# Power_test.net
KiCad netlist of a schematic drawn in Altium Designer
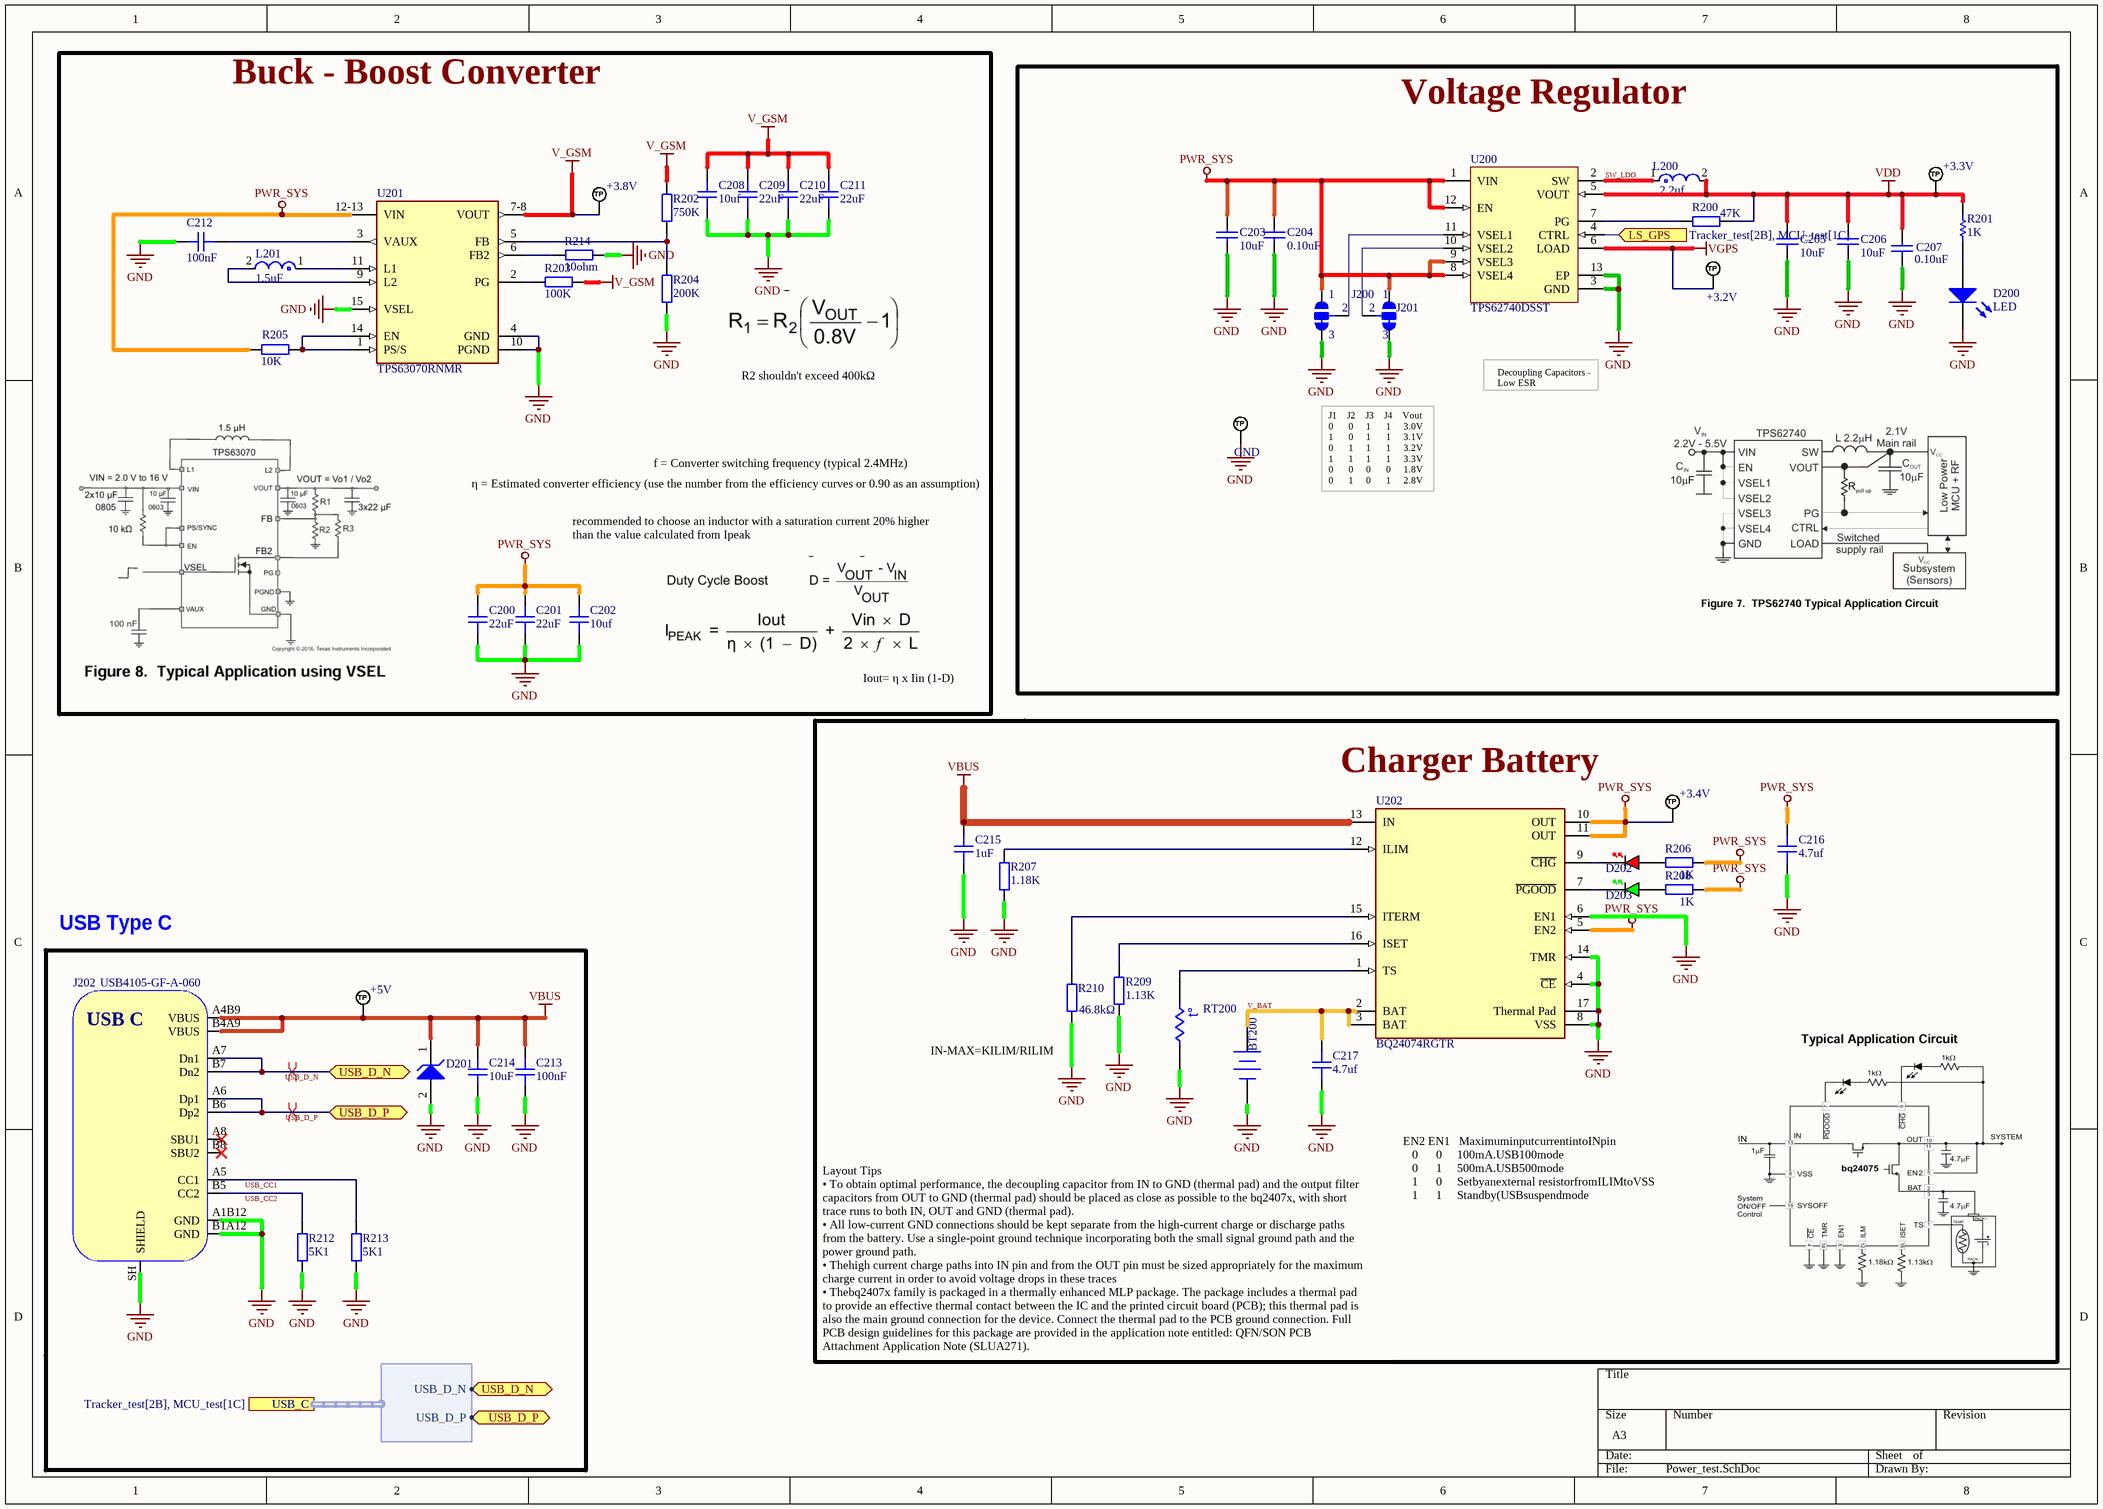
[diagram p0: Power_test.SchDoc]

(export (version "E")
  (design (tool "Eeschema 10.0.6"))
  (components
    (comp (ref "+3.2V")
      (value "TP_NOBOM")
      (footprint "PAD_RND_1MM")
      (description "Test Point Round 1mm (NO BOM)")
      (libsource (lib "PhilsLab_Library") (part "TEST_POINT_RND_1MM"))
    )
    (comp (ref "+3.3V")
      (value "TP_NOBOM")
      (footprint "PAD_RND_1MM")
      (description "Test Point Round 1mm (NO BOM)")
      (libsource (lib "PhilsLab_Library") (part "TEST_POINT_RND_1MM"))
    )
    (comp (ref "+3.4V")
      (value "TP_NOBOM")
      (footprint "PAD_RND_1MM")
      (description "Test Point Round 1mm (NO BOM)")
      (libsource (lib "PhilsLab_Library") (part "TEST_POINT_RND_1MM"))
    )
    (comp (ref "+3.8V")
      (value "TP_NOBOM")
      (footprint "PAD_RND_1MM")
      (description "Test Point Round 1mm (NO BOM)")
      (libsource (lib "PhilsLab_Library") (part "TEST_POINT_RND_1MM"))
    )
    (comp (ref "+5V")
      (value "TP_NOBOM")
      (footprint "PAD_RND_1MM")
      (description "Test Point Round 1mm (NO BOM)")
      (libsource (lib "PhilsLab_Library") (part "TEST_POINT_RND_1MM"))
    )
    (comp (ref "BT200")
      (value "Battery")
      (footprint "BAT-2")
      (description "Multicell Battery")
      (fields (field (name "PUBLISHER") "Altium Limited"))
      (libsource (lib "Miscellaneous+Devices") (part "Battery"))
    )
    (comp (ref "C200")
      (value "22uF")
      (footprint "CAP_0805")
      (description "Capacitor SMD 0805")
      (libsource (lib "PhilsLab_Library") (part "CAP_0805"))
    )
    (comp (ref "C201")
      (value "22uF")
      (footprint "CAP_0805")
      (description "Capacitor SMD 0805")
      (libsource (lib "PhilsLab_Library") (part "CAP_0805"))
    )
    (comp (ref "C202")
      (value "10uf")
      (footprint "CAP_0603")
      (description "Capacitor SMD 0603")
      (libsource (lib "PhilsLab_Library") (part "CAP_0603"))
    )
    (comp (ref "C203")
      (value "10uF")
      (footprint "C0402 - duplicate")
      (description "CAP CER 10UF 10V X5R 0402")
      (fields
        (field (name "PART NUMBER") "C00062")
        (field (name "MANUFACTURER") "KEMET - Electronic Component")
      )
      (libsource (lib "intrgrat_lib") (part "CAP"))
    )
    (comp (ref "C204")
      (value "0.10uF")
      (footprint "C0402")
      (description "CAP CER 0.1UF 10V X5R 0402")
      (fields
        (field (name "PART NUMBER") "C00062")
        (field (name "MANUFACTURER") "KEMET - Electronic Component")
      )
      (libsource (lib "intrgrat_lib") (part "CAP_2"))
    )
    (comp (ref "C205")
      (value "10uF")
      (footprint "C0402 - duplicate")
      (description "CAP CER 10UF 10V X5R 0402")
      (fields
        (field (name "PART NUMBER") "C00062")
        (field (name "MANUFACTURER") "KEMET - Electronic Component")
      )
      (libsource (lib "intrgrat_lib") (part "CAP"))
    )
    (comp (ref "C206")
      (value "10uF")
      (footprint "C0402 - duplicate")
      (description "CAP CER 10UF 10V X5R 0402")
      (fields
        (field (name "PART NUMBER") "C00062")
        (field (name "MANUFACTURER") "KEMET - Electronic Component")
      )
      (libsource (lib "intrgrat_lib") (part "CAP"))
    )
    (comp (ref "C207")
      (value "0.10uF")
      (footprint "C0402")
      (description "CAP CER 0.1UF 10V X5R 0402")
      (fields
        (field (name "PART NUMBER") "C00062")
        (field (name "MANUFACTURER") "KEMET - Electronic Component")
      )
      (libsource (lib "intrgrat_lib") (part "CAP_2"))
    )
    (comp (ref "C208")
      (value "10uf")
      (footprint "CAP_0603")
      (description "Capacitor SMD 0603")
      (libsource (lib "PhilsLab_Library") (part "CAP_0603"))
    )
    (comp (ref "C209")
      (value "22uF")
      (footprint "CAP_0805")
      (description "Capacitor SMD 0805")
      (libsource (lib "PhilsLab_Library") (part "CAP_0805"))
    )
    (comp (ref "C210")
      (value "22uF")
      (footprint "CAP_0805")
      (description "Capacitor SMD 0805")
      (libsource (lib "PhilsLab_Library") (part "CAP_0805"))
    )
    (comp (ref "C211")
      (value "22uF")
      (footprint "CAP_0805")
      (description "Capacitor SMD 0805")
      (libsource (lib "PhilsLab_Library") (part "CAP_0805"))
    )
    (comp (ref "C212")
      (value "100nF")
      (footprint "CAP_0603")
      (description "Capacitor SMD 0603")
      (libsource (lib "PhilsLab_Library") (part "CAP_0603"))
    )
    (comp (ref "C213")
      (value "100nF")
      (footprint "CAP_0402")
      (description "Capacitor SMD 0402")
      (libsource (lib "PhilsLab_Library") (part "CAP_0402"))
    )
    (comp (ref "C214")
      (value "10uF")
      (footprint "CAP_0402")
      (description "Capacitor SMD 0402")
      (libsource (lib "PhilsLab_Library") (part "CAP_0402"))
    )
    (comp (ref "C215")
      (value "1uF")
      (footprint "CAP_0402")
      (description "Capacitor SMD 0402")
      (libsource (lib "PhilsLab_Library") (part "CAP_0402"))
    )
    (comp (ref "C216")
      (value "4.7uf")
      (footprint "CAP_0402")
      (description "Capacitor SMD 0402")
      (libsource (lib "PhilsLab_Library") (part "CAP_0402"))
    )
    (comp (ref "C217")
      (value "4.7uf")
      (footprint "CAP_0402")
      (description "Capacitor SMD 0402")
      (libsource (lib "PhilsLab_Library") (part "CAP_0402"))
    )
    (comp (ref "D200")
      (value "LED")
      (footprint "LED-0603-R")
      (description "Typical RED GaAs LED")
      (fields
        (field (name "MANUFACTURER") "Lite-On Inc.")
        (field (name "PARTNUMBER") "LTST-C190GKT")
        (field (name "PUBLISHER") "Walid Balid")
      )
      (libsource (lib "intrgrat_lib") (part "LED"))
    )
    (comp (ref "D201")
      (value "SZSMF6.0AT1G")
      (footprint "ONSC-SOD-123FL-2-498_V")
      (description "200 W Transient Voltage Suppressor, 2-Pin SOD-123FL, Pb-Free, Tape and Reel")
      (fields (field (name "MANUFACTURER") "On Semiconductor"))
      (libsource (lib "Altium Content Vault") (part "ONSC-K1A2-2"))
    )
    (comp (ref "D202")
      (value "RED")
      (footprint "LED_0402_RED")
      (description "LED 0402 RED SMD")
      (libsource (lib "PhilsLab_Library") (part "LED_0402_RED"))
    )
    (comp (ref "D203")
      (value "GREEN")
      (footprint "LED_0402_GREEN")
      (description "LED 0402 GREEN SMD")
      (libsource (lib "PhilsLab_Library") (part "LED_0402_GREEN"))
    )
    (comp (ref "GND")
      (value "TP_NOBOM")
      (footprint "PAD_RND_1MM")
      (description "Test Point Round 1mm (NO BOM)")
      (libsource (lib "PhilsLab_Library") (part "TEST_POINT_RND_1MM"))
    )
    (comp (ref "J200")
      (value "JUMPER-3-PAD")
      (footprint "JUMPER-3-NC")
      (libsource (lib "intrgrat_lib") (part "JUMPER-3-PAD"))
    )
    (comp (ref "J201")
      (value "JUMPER-3-PAD")
      (footprint "JUMPER-3-NC")
      (libsource (lib "") (part "JUMPER-3-PAD_1"))
    )
    (comp (ref "J202")
      (value "USB4105-GF-A-060")
      (footprint "USB4105-GF-A-060")
      (description "USB Connector Type C SMT 12 Pin")
      (fields (field (name "MANUFACTURER") "GCT"))
      (libsource (lib "Schematic-Lib-PhilsLab") (part "USB4105-GF-A-060"))
    )
    (comp (ref "L200")
      (value "2.2uf")
      (footprint "FP-LPS3314-MFG")
      (libsource (lib "Altium Content Vault") (part "4cc4b267dca4c8e51f7102f422741d8"))
    )
    (comp (ref "L201")
      (value "1.5uF")
      (footprint "FP-XFL4020-MFG")
      (fields (field (name "TOLERANCE") "20%"))
      (libsource (lib "") (part "4cc4b267dca4c8e51f7102f422741d8_1"))
    )
    (comp (ref "R200")
      (value "47K")
      (footprint "RES_0402")
      (description "Resistor SMD 0402")
      (libsource (lib "PhilsLab_Library") (part "RES_0402"))
    )
    (comp (ref "R201")
      (value "1K")
      (footprint "R0402")
      (description "RES SMD 1K OHM 5% 1/16W 0402")
      (fields (field (name "PART NUMBER") "R00007") (field (name "MANUFACTURER") "Yageo"))
      (libsource (lib "intrgrat_lib") (part "RES"))
    )
    (comp (ref "R202")
      (value "750K")
      (footprint "RES_0402")
      (description "Resistor SMD 0402")
      (libsource (lib "PhilsLab_Library") (part "RES_0402"))
    )
    (comp (ref "R203")
      (value "100K")
      (footprint "RES_0402")
      (description "Resistor SMD 0402")
      (libsource (lib "PhilsLab_Library") (part "RES_0402"))
    )
    (comp (ref "R204")
      (value "200K")
      (footprint "RES_0402")
      (description "Resistor SMD 0402")
      (libsource (lib "PhilsLab_Library") (part "RES_0402"))
    )
    (comp (ref "R205")
      (value "10K")
      (footprint "RES_0402")
      (description "Resistor SMD 0402")
      (libsource (lib "PhilsLab_Library") (part "RES_0402"))
    )
    (comp (ref "R206")
      (value "1K")
      (footprint "RES_0402")
      (description "Resistor SMD 0402")
      (libsource (lib "PhilsLab_Library") (part "RES_0402"))
    )
    (comp (ref "R207")
      (value "1.18K")
      (footprint "RES_0402")
      (description "Resistor SMD 0402")
      (libsource (lib "PhilsLab_Library") (part "RES_0402"))
    )
    (comp (ref "R208")
      (value "1K")
      (footprint "RES_0402")
      (description "Resistor SMD 0402")
      (libsource (lib "PhilsLab_Library") (part "RES_0402"))
    )
    (comp (ref "R209")
      (value "1.13K")
      (footprint "RES_0402")
      (description "Resistor SMD 0402")
      (libsource (lib "PhilsLab_Library") (part "RES_0402"))
    )
    (comp (ref "R210")
      (value "46.8kΩ")
      (footprint "RES_0402")
      (description "Resistor SMD 0402")
      (libsource (lib "PhilsLab_Library") (part "RES_0402"))
    )
    (comp (ref "R212")
      (value "5K1")
      (footprint "RES_0603")
      (description "Resistor SMD 0603")
      (libsource (lib "Schematic-Lib-PhilsLab") (part "RES_0603"))
    )
    (comp (ref "R213")
      (value "5K1")
      (footprint "RES_0603")
      (description "Resistor SMD 0603")
      (libsource (lib "Schematic-Lib-PhilsLab") (part "RES_0603"))
    )
    (comp (ref "R214")
      (value "10ohm")
      (footprint "RES_0402")
      (description "Resistor SMD 0402")
      (libsource (lib "PhilsLab_Library") (part "RES_0402"))
    )
    (comp (ref "RT200")
      (value "Res Thermal")
      (footprint "6-0805_N")
      (description "Thermistor")
      (fields (field (name "PUBLISHER") "Altium Limited"))
      (libsource (lib "intrgrat_lib") (part "Res Thermal"))
    )
    (comp (ref "U200")
      (value "TPS62740DSST")
      (footprint "DSS0012A_V")
      (fields (field (name "PARTNUMBER") "TPS62740"))
      (libsource (lib "intrgrat_lib") (part "CMP-0323-00573-2"))
    )
    (comp (ref "U201")
      (value "TPS63070RNMR")
      (footprint "FP-RNM0015A-MFG")
      (description "IC REG BCK BST ADJ 3.6A 15VQFN")
      (libsource (lib "intrgrat_lib") (part "CMP-04918-000409-1"))
    )
    (comp (ref "U202")
      (value "BQ24074RGTR")
      (footprint "FP-RGT0016C-MFG")
      (description "IC LI-ION CHARGE MGMT 16-QFN")
      (libsource (lib "intrgrat_lib") (part "CMP-0321-00220-3"))
    )
  )
  (nets
    (net (code "2") (name "/LS_GPS") (class "Default")
      (node (ref "U200") (pin "4") (pinfunction "CTRL_4") (pintype "input"))
    )
    (net (code "3") (name "/SW_LDO") (class "Default")
      (node (ref "L200") (pin "1") (pinfunction "1_1") (pintype "passive"))
      (node (ref "U200") (pin "2") (pinfunction "SW_2") (pintype "power_in"))
    )
    (net (code "4") (name "/USB_CC1") (class "Default")
      (node (ref "J202") (pin "A5") (pinfunction "CC1_A5") (pintype "passive"))
      (node (ref "R213") (pin "2") (pinfunction "2_2") (pintype "passive"))
    )
    (net (code "5") (name "/USB_CC2") (class "Default")
      (node (ref "J202") (pin "B5") (pinfunction "CC2_B5") (pintype "passive"))
      (node (ref "R212") (pin "2") (pinfunction "2_2") (pintype "passive"))
    )
    (net (code "6") (name "/USB_D_N") (class "Default")
      (node (ref "J202") (pin "A7") (pinfunction "Dn1_A7") (pintype "passive"))
      (node (ref "J202") (pin "B7") (pinfunction "Dn2_B7") (pintype "passive"))
    )
    (net (code "7") (name "/USB_D_P") (class "Default")
      (node (ref "J202") (pin "A6") (pinfunction "Dp1_A6") (pintype "passive"))
      (node (ref "J202") (pin "B6") (pinfunction "Dp2_B6") (pintype "passive"))
    )
    (net (code "8") (name "/V_BAT") (class "Default")
      (node (ref "BT200") (pin "1") (pinfunction "+_1") (pintype "passive"))
      (node (ref "C217") (pin "1") (pinfunction "1_1") (pintype "passive"))
      (node (ref "U202") (pin "2") (pinfunction "BAT_2") (pintype "power_in"))
      (node (ref "U202") (pin "3") (pinfunction "BAT_3") (pintype "power_in"))
    )
    (net (code "10") (name "GND") (class "Default")
      (node (ref "BT200") (pin "2") (pinfunction "-_2") (pintype "passive"))
      (node (ref "C200") (pin "1") (pinfunction "1_1") (pintype "passive"))
      (node (ref "C201") (pin "1") (pinfunction "1_1") (pintype "passive"))
      (node (ref "C202") (pin "1") (pinfunction "1_1") (pintype "passive"))
      (node (ref "C203") (pin "2") (pinfunction "2_2") (pintype "passive"))
      (node (ref "C204") (pin "2") (pinfunction "2_2") (pintype "passive"))
      (node (ref "C205") (pin "2") (pinfunction "2_2") (pintype "passive"))
      (node (ref "C206") (pin "2") (pinfunction "2_2") (pintype "passive"))
      (node (ref "C207") (pin "2") (pinfunction "2_2") (pintype "passive"))
      (node (ref "C208") (pin "1") (pinfunction "1_1") (pintype "passive"))
      (node (ref "C209") (pin "1") (pinfunction "1_1") (pintype "passive"))
      (node (ref "C210") (pin "1") (pinfunction "1_1") (pintype "passive"))
      (node (ref "C211") (pin "1") (pinfunction "1_1") (pintype "passive"))
      (node (ref "C212") (pin "1") (pinfunction "1_1") (pintype "passive"))
      (node (ref "C213") (pin "1") (pinfunction "1_1") (pintype "passive"))
      (node (ref "C214") (pin "1") (pinfunction "1_1") (pintype "passive"))
      (node (ref "C215") (pin "1") (pinfunction "1_1") (pintype "passive"))
      (node (ref "C216") (pin "2") (pinfunction "2_2") (pintype "passive"))
      (node (ref "C217") (pin "2") (pinfunction "2_2") (pintype "passive"))
      (node (ref "D200") (pin "2") (pinfunction "K_2") (pintype "passive"))
      (node (ref "D201") (pin "2") (pinfunction "A_2") (pintype "passive"))
      (node (ref "GND") (pin "1") (pinfunction "TP_1") (pintype "passive"))
      (node (ref "J200") (pin "3") (pinfunction "3_3") (pintype "passive"))
      (node (ref "J201") (pin "3") (pinfunction "3_3") (pintype "passive"))
      (node (ref "J202") (pin "A1B12") (pinfunction "GND_A1B12") (pintype "passive"))
      (node (ref "J202") (pin "B1A12") (pinfunction "GND_B1A12") (pintype "passive"))
      (node (ref "J202") (pin "SH") (pinfunction "SHIELD_SH") (pintype "passive"))
      (node (ref "R204") (pin "1") (pinfunction "1_1") (pintype "passive"))
      (node (ref "R207") (pin "1") (pinfunction "1_1") (pintype "passive"))
      (node (ref "R209") (pin "1") (pinfunction "1_1") (pintype "passive"))
      (node (ref "R210") (pin "2") (pinfunction "2_2") (pintype "passive"))
      (node (ref "R212") (pin "1") (pinfunction "1_1") (pintype "passive"))
      (node (ref "R213") (pin "1") (pinfunction "1_1") (pintype "passive"))
      (node (ref "R214") (pin "1") (pinfunction "1_1") (pintype "passive"))
      (node (ref "RT200") (pin "2") (pinfunction "2_2") (pintype "passive"))
      (node (ref "U200") (pin "13") (pinfunction "EP_13") (pintype "power_in"))
      (node (ref "U200") (pin "3") (pinfunction "GND_3") (pintype "power_in"))
      (node (ref "U201") (pin "10") (pinfunction "PGND_10") (pintype "power_in"))
      (node (ref "U201") (pin "15") (pinfunction "VSEL_15") (pintype "input"))
      (node (ref "U201") (pin "4") (pinfunction "GND_4") (pintype "power_in"))
      (node (ref "U202") (pin "14") (pinfunction "TMR_14") (pintype "input"))
      (node (ref "U202") (pin "17") (pinfunction "Thermal_Pad_17") (pintype "power_in"))
      (node (ref "U202") (pin "4") (pinfunction "~{CE}_4") (pintype "input"))
      (node (ref "U202") (pin "6") (pinfunction "EN1_6") (pintype "input"))
      (node (ref "U202") (pin "8") (pinfunction "VSS_8") (pintype "power_in"))
    )
    (net (code "11") (name "Net-(D200-A)") (class "Default")
      (node (ref "D200") (pin "1") (pinfunction "A_1") (pintype "passive"))
      (node (ref "R201") (pin "2") (pinfunction "2_2") (pintype "passive"))
    )
    (net (code "12") (name "Net-(D202-PadA)") (class "Default")
      (node (ref "D202") (pin "A") (pinfunction "A_A") (pintype "passive"))
      (node (ref "R206") (pin "1") (pinfunction "1_1") (pintype "passive"))
    )
    (net (code "13") (name "Net-(D203-PadA)") (class "Default")
      (node (ref "D203") (pin "A") (pinfunction "A_A") (pintype "passive"))
      (node (ref "R208") (pin "1") (pinfunction "1_1") (pintype "passive"))
    )
    (net (code "14") (name "Net-(U200-PG)") (class "Default")
      (node (ref "R200") (pin "1") (pinfunction "1_1") (pintype "passive"))
      (node (ref "U200") (pin "7") (pinfunction "PG_7") (pintype "tri_state"))
    )
    (net (code "15") (name "Net-(U200-VSEL1)") (class "Default")
      (node (ref "J200") (pin "2") (pinfunction "2_2") (pintype "passive"))
      (node (ref "U200") (pin "11") (pinfunction "VSEL1_11") (pintype "input"))
    )
    (net (code "16") (name "Net-(U200-VSEL2)") (class "Default")
      (node (ref "J201") (pin "2") (pinfunction "2_2") (pintype "passive"))
      (node (ref "U200") (pin "10") (pinfunction "VSEL2_10") (pintype "input"))
    )
    (net (code "17") (name "Net-(U201-EN)") (class "Default")
      (node (ref "R205") (pin "2") (pinfunction "2_2") (pintype "passive"))
      (node (ref "U201") (pin "1") (pinfunction "PS/S_1") (pintype "input"))
      (node (ref "U201") (pin "14") (pinfunction "EN_14") (pintype "input"))
    )
    (net (code "18") (name "Net-(U201-FB)") (class "Default")
      (node (ref "R202") (pin "1") (pinfunction "1_1") (pintype "passive"))
      (node (ref "R204") (pin "2") (pinfunction "2_2") (pintype "passive"))
      (node (ref "U201") (pin "5") (pinfunction "FB_5") (pintype "output"))
    )
    (net (code "19") (name "Net-(U201-FB2)") (class "Default")
      (node (ref "R214") (pin "2") (pinfunction "2_2") (pintype "passive"))
      (node (ref "U201") (pin "6") (pinfunction "FB2_6") (pintype "output"))
    )
    (net (code "20") (name "Net-(U201-L1)") (class "Default")
      (node (ref "L201") (pin "1") (pinfunction "1_1") (pintype "passive"))
      (node (ref "U201") (pin "11") (pinfunction "L1_11") (pintype "input"))
    )
    (net (code "21") (name "Net-(U201-L2)") (class "Default")
      (node (ref "L201") (pin "2") (pinfunction "2_2") (pintype "passive"))
      (node (ref "U201") (pin "9") (pinfunction "L2_9") (pintype "input"))
    )
    (net (code "22") (name "Net-(U201-PG)") (class "Default")
      (node (ref "R203") (pin "2") (pinfunction "2_2") (pintype "passive"))
      (node (ref "U201") (pin "2") (pinfunction "PG_2") (pintype "open_collector"))
    )
    (net (code "23") (name "Net-(U201-VAUX)") (class "Default")
      (node (ref "C212") (pin "2") (pinfunction "2_2") (pintype "passive"))
      (node (ref "U201") (pin "3") (pinfunction "VAUX_3") (pintype "output"))
    )
    (net (code "24") (name "Net-(U202-ILIM)") (class "Default")
      (node (ref "R207") (pin "2") (pinfunction "2_2") (pintype "passive"))
      (node (ref "U202") (pin "12") (pinfunction "ILIM_12") (pintype "input"))
    )
    (net (code "25") (name "Net-(U202-ISET)") (class "Default")
      (node (ref "R209") (pin "2") (pinfunction "2_2") (pintype "passive"))
      (node (ref "U202") (pin "16") (pinfunction "ISET_16") (pintype "input"))
    )
    (net (code "26") (name "Net-(U202-ITERM)") (class "Default")
      (node (ref "R210") (pin "1") (pinfunction "1_1") (pintype "passive"))
      (node (ref "U202") (pin "15") (pinfunction "ITERM_15") (pintype "input"))
    )
    (net (code "27") (name "Net-(U202-TS)") (class "Default")
      (node (ref "RT200") (pin "1") (pinfunction "1_1") (pintype "passive"))
      (node (ref "U202") (pin "1") (pinfunction "TS_1") (pintype "input"))
    )
    (net (code "28") (name "Net-(U202-~{CHG})") (class "Default")
      (node (ref "D202") (pin "K") (pinfunction "K_K") (pintype "passive"))
      (node (ref "U202") (pin "9") (pinfunction "~{CHG}_9") (pintype "tri_state"))
    )
    (net (code "29") (name "Net-(U202-~{PGOOD})") (class "Default")
      (node (ref "D203") (pin "K") (pinfunction "K_K") (pintype "passive"))
      (node (ref "U202") (pin "7") (pinfunction "~{PGOOD}_7") (pintype "tri_state"))
    )
    (net (code "30") (name "PWR_SYS") (class "Default")
      (node (ref "+3.4V") (pin "1") (pinfunction "TP_1") (pintype "passive"))
      (node (ref "C200") (pin "2") (pinfunction "2_2") (pintype "passive"))
      (node (ref "C201") (pin "2") (pinfunction "2_2") (pintype "passive"))
      (node (ref "C202") (pin "2") (pinfunction "2_2") (pintype "passive"))
      (node (ref "C203") (pin "1") (pinfunction "1_1") (pintype "passive"))
      (node (ref "C204") (pin "1") (pinfunction "1_1") (pintype "passive"))
      (node (ref "C216") (pin "1") (pinfunction "1_1") (pintype "passive"))
      (node (ref "J200") (pin "1") (pinfunction "1_1") (pintype "passive"))
      (node (ref "J201") (pin "1") (pinfunction "1_1") (pintype "passive"))
      (node (ref "R205") (pin "1") (pinfunction "1_1") (pintype "passive"))
      (node (ref "R206") (pin "2") (pinfunction "2_2") (pintype "passive"))
      (node (ref "R208") (pin "2") (pinfunction "2_2") (pintype "passive"))
      (node (ref "U200") (pin "1") (pinfunction "VIN_1") (pintype "power_in"))
      (node (ref "U200") (pin "12") (pinfunction "EN_12") (pintype "input"))
      (node (ref "U200") (pin "8") (pinfunction "VSEL4_8") (pintype "input"))
      (node (ref "U200") (pin "9") (pinfunction "VSEL3_9") (pintype "input"))
      (node (ref "U201") (pin "12-13") (pinfunction "VIN_12-13") (pintype "power_in"))
      (node (ref "U202") (pin "10") (pinfunction "OUT_10") (pintype "power_in"))
      (node (ref "U202") (pin "11") (pinfunction "OUT_11") (pintype "power_in"))
      (node (ref "U202") (pin "5") (pinfunction "EN2_5") (pintype "input"))
    )
    (net (code "31") (name "VBUS") (class "Default")
      (node (ref "+5V") (pin "1") (pinfunction "TP_1") (pintype "passive"))
      (node (ref "C213") (pin "2") (pinfunction "2_2") (pintype "passive"))
      (node (ref "C214") (pin "2") (pinfunction "2_2") (pintype "passive"))
      (node (ref "C215") (pin "2") (pinfunction "2_2") (pintype "passive"))
      (node (ref "D201") (pin "1") (pinfunction "K_1") (pintype "passive"))
      (node (ref "J202") (pin "A4B9") (pinfunction "VBUS_A4B9") (pintype "passive"))
      (node (ref "J202") (pin "B4A9") (pinfunction "VBUS_B4A9") (pintype "passive"))
      (node (ref "U202") (pin "13") (pinfunction "IN_13") (pintype "power_in"))
    )
    (net (code "32") (name "VDD") (class "Default")
      (node (ref "+3.3V") (pin "1") (pinfunction "TP_1") (pintype "passive"))
      (node (ref "C205") (pin "1") (pinfunction "1_1") (pintype "passive"))
      (node (ref "C206") (pin "1") (pinfunction "1_1") (pintype "passive"))
      (node (ref "C207") (pin "1") (pinfunction "1_1") (pintype "passive"))
      (node (ref "L200") (pin "2") (pinfunction "2_2") (pintype "passive"))
      (node (ref "R200") (pin "2") (pinfunction "2_2") (pintype "passive"))
      (node (ref "R201") (pin "1") (pinfunction "1_1") (pintype "passive"))
      (node (ref "U200") (pin "5") (pinfunction "VOUT_5") (pintype "input"))
    )
    (net (code "33") (name "VGPS") (class "Default")
      (node (ref "+3.2V") (pin "1") (pinfunction "TP_1") (pintype "passive"))
      (node (ref "U200") (pin "6") (pinfunction "LOAD_6") (pintype "power_in"))
    )
    (net (code "34") (name "V_GSM") (class "Default")
      (node (ref "+3.8V") (pin "1") (pinfunction "TP_1") (pintype "passive"))
      (node (ref "C208") (pin "2") (pinfunction "2_2") (pintype "passive"))
      (node (ref "C209") (pin "2") (pinfunction "2_2") (pintype "passive"))
      (node (ref "C210") (pin "2") (pinfunction "2_2") (pintype "passive"))
      (node (ref "C211") (pin "2") (pinfunction "2_2") (pintype "passive"))
      (node (ref "R202") (pin "2") (pinfunction "2_2") (pintype "passive"))
      (node (ref "R203") (pin "1") (pinfunction "1_1") (pintype "passive"))
      (node (ref "U201") (pin "7-8") (pinfunction "VOUT_7-8") (pintype "output"))
    )
    (net (code "35") (name "unconnected-(J202-SBU1-PadA8)") (class "Default")
      (node (ref "J202") (pin "A8") (pinfunction "SBU1_A8") (pintype "passive+no_connect"))
    )
    (net (code "36") (name "unconnected-(J202-SBU2-PadB8)") (class "Default")
      (node (ref "J202") (pin "B8") (pinfunction "SBU2_B8") (pintype "passive+no_connect"))
    )
  )
)
